# TTFT.net
KiCad netlist of a schematic drawn in Altium Designer
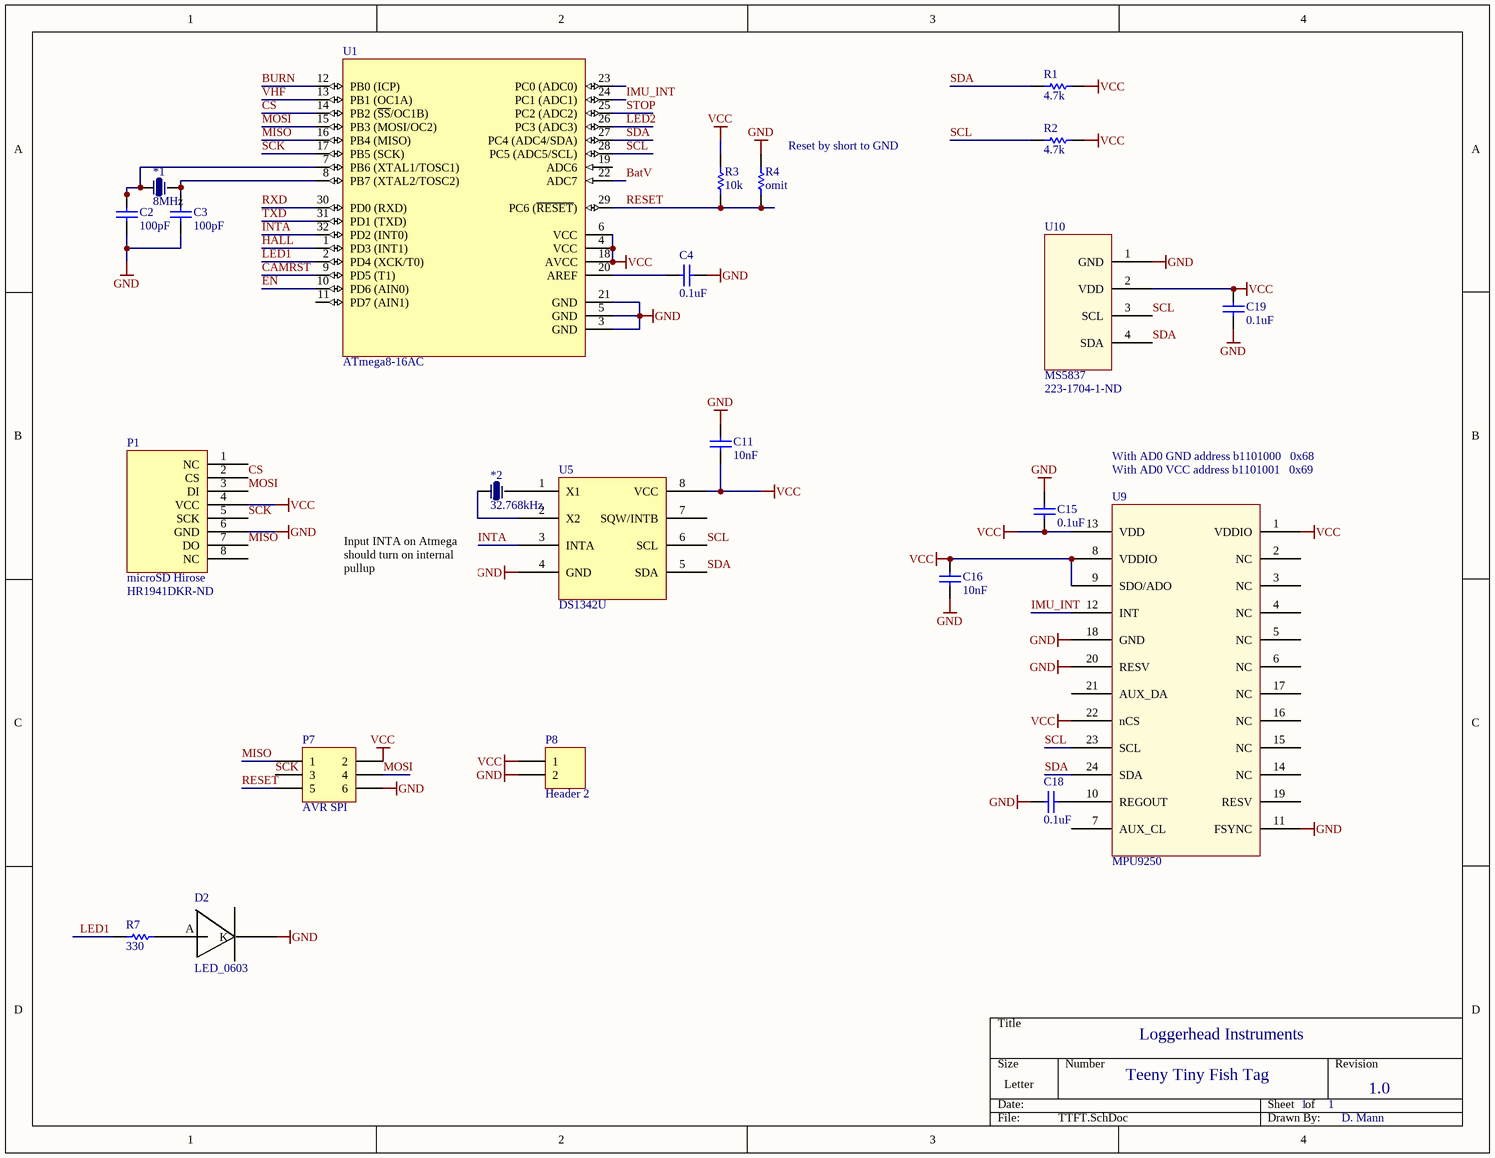
[diagram p0: TTFT.SchDoc]

(export (version "E")
  (design (tool "Eeschema 10.0.6"))
  (components
    (comp (ref "*1") (value "8MHz") (footprint "XTAL-ABM3") (libsource (lib "Loggerhead") (part "XTAL-ABM3")))
    (comp (ref "*2")
      (value "32.768kHz")
      (footprint "XTAL-ABS06")
      (libsource (lib "Loggerhead") (part "XTAL_ABS06"))
    )
    (comp (ref "C2")
      (value "100pF")
      (footprint "0402")
      (description "Ceramic Chip Capacitor - Standard")
      (fields (field (name "PUBLISHER") "Altium Limited"))
      (libsource (lib "KEMET Chip Capacitor") (part "C0402"))
    )
    (comp (ref "C3")
      (value "100pF")
      (footprint "0402")
      (description "Ceramic Chip Capacitor - Standard")
      (fields (field (name "PUBLISHER") "Altium Limited"))
      (libsource (lib "KEMET Chip Capacitor") (part "C0402"))
    )
    (comp (ref "C4")
      (value "0.1uF")
      (footprint "0402")
      (description "Ceramic Chip Capacitor - Standard")
      (fields (field (name "PUBLISHER") "Altium Limited"))
      (libsource (lib "KEMET Chip Capacitor") (part "C0402"))
    )
    (comp (ref "C11")
      (value "10nF")
      (footprint "0402")
      (description "Ceramic Chip Capacitor - Standard")
      (fields (field (name "PUBLISHER") "Altium Limited"))
      (libsource (lib "KEMET Chip Capacitor") (part "C0402"))
    )
    (comp (ref "C15")
      (value "0.1uF")
      (footprint "0402")
      (description "Ceramic Chip Capacitor - Standard")
      (fields (field (name "PUBLISHER") "Altium Limited"))
      (libsource (lib "KEMET Chip Capacitor") (part "C0402"))
    )
    (comp (ref "C16")
      (value "10nF")
      (footprint "0402")
      (description "Ceramic Chip Capacitor - Standard")
      (fields (field (name "PUBLISHER") "Altium Limited"))
      (libsource (lib "KEMET Chip Capacitor") (part "C0402"))
    )
    (comp (ref "C18")
      (value "0.1uF")
      (footprint "0402")
      (description "Ceramic Chip Capacitor - Standard")
      (fields (field (name "PUBLISHER") "Altium Limited"))
      (libsource (lib "KEMET Chip Capacitor") (part "C0402"))
    )
    (comp (ref "C19")
      (value "0.1uF")
      (footprint "0402")
      (description "Ceramic Chip Capacitor - Standard")
      (fields (field (name "PUBLISHER") "Altium Limited"))
      (libsource (lib "KEMET Chip Capacitor") (part "C0402"))
    )
    (comp (ref "D2")
      (value "LED_0603")
      (footprint "Diode0603")
      (libsource (lib "Loggerhead") (part "LED_0603"))
    )
    (comp (ref "P1")
      (value "microSD Hirose")
      (footprint "DM3D microSD")
      (fields (field (name "SUPPLIER PART NUMBER 1") "HR1941DKR-ND"))
      (libsource (lib "Loggerhead") (part "microSD Hirose"))
    )
    (comp (ref "P7")
      (value "AVR SPI")
      (footprint "HDR2X3")
      (description "Header, 3-Pin, Dual row")
      (fields (field (name "PUBLISHER") "Altium Limited"))
      (libsource (lib "Miscellaneous Connectors") (part "Header 3X2"))
    )
    (comp (ref "P8")
      (value "Header 2")
      (footprint "HDR1X2")
      (description "Header, 2-Pin")
      (fields (field (name "PUBLISHER") "Altium Limited"))
      (libsource (lib "Miscellaneous Connectors") (part "Header 2"))
    )
    (comp (ref "R1")
      (value "4.7k")
      (footprint "3-0603")
      (fields (field (name "PUBLISHER") "Altium Limited"))
      (libsource (lib "Panasonic Resistor") (part "ERJ3RK"))
    )
    (comp (ref "R2")
      (value "4.7k")
      (footprint "3-0603")
      (fields (field (name "PUBLISHER") "Altium Limited"))
      (libsource (lib "Panasonic Resistor") (part "ERJ3RK"))
    )
    (comp (ref "R3")
      (value "10k")
      (footprint "3-0603")
      (fields (field (name "PUBLISHER") "Altium Limited"))
      (libsource (lib "Panasonic Resistor") (part "ERJ3RK"))
    )
    (comp (ref "R4")
      (value "omit")
      (footprint "3-0603")
      (fields (field (name "PUBLISHER") "Altium Limited"))
      (libsource (lib "Panasonic Resistor") (part "ERJ3RK"))
    )
    (comp (ref "R7")
      (value "330")
      (footprint "3-0603")
      (fields (field (name "PUBLISHER") "Altium Limited"))
      (libsource (lib "Panasonic Resistor") (part "ERJ3RK"))
    )
    (comp (ref "U1")
      (value "ATmega8-16AC")
      (footprint "32M1-A_M")
      (description "8-Bit AVR Microcontroller with 8K Bytes of In-System Programmable Flash Memory")
      (fields (field (name "PUBLISHER") "Altium Limited"))
      (libsource (lib "Atmel Microcontroller 8-Bit AVR") (part "ATmega8-16AC"))
    )
    (comp (ref "U5") (value "DS1342U") (footprint "uSOP8") (libsource (lib "Loggerhead") (part "DS1337")))
    (comp (ref "U9")
      (value "MPU9250")
      (footprint "MPU6500")
      (description "Invensense")
      (libsource (lib "Loggerhead") (part "MPU-9250"))
    )
    (comp (ref "U10")
      (value "MS5837")
      (footprint "MS5837")
      (description "Pressure/Temp")
      (fields (field (name "SUPPLIER PART NUMBER 1") "223-1704-1-ND"))
      (libsource (lib "Loggerhead") (part "MS5837"))
    )
  )
  (nets
    (net (code "1") (name "/BURN") (class "Default")
      (node (ref "U1") (pin "12") (pinfunction "PB0_(ICP)_12") (pintype "bidirectional"))
    )
    (net (code "2") (name "/BatV") (class "Default")
      (node (ref "U1") (pin "22") (pinfunction "ADC7_22") (pintype "input"))
    )
    (net (code "3") (name "/CAMRST") (class "Default")
      (node (ref "U1") (pin "9") (pinfunction "PD5_(T1)_9") (pintype "bidirectional"))
    )
    (net (code "4") (name "/CS") (class "Default")
      (node (ref "P1") (pin "2") (pinfunction "CS_2") (pintype "passive"))
      (node (ref "U1") (pin "14") (pinfunction "PB2_(~{SS}/OC1B)_14") (pintype "bidirectional"))
    )
    (net (code "5") (name "/EN") (class "Default")
      (node (ref "U1") (pin "10") (pinfunction "PD6_(AIN0)_10") (pintype "bidirectional"))
    )
    (net (code "6") (name "/HALL") (class "Default")
      (node (ref "U1") (pin "1") (pinfunction "PD3_(INT1)_1") (pintype "bidirectional"))
    )
    (net (code "7") (name "/IMU_INT") (class "Default")
      (node (ref "U1") (pin "24") (pinfunction "PC1_(ADC1)_24") (pintype "bidirectional"))
      (node (ref "U9") (pin "12") (pinfunction "INT_12") (pintype "passive"))
    )
    (net (code "8") (name "/INTA") (class "Default")
      (node (ref "U1") (pin "32") (pinfunction "PD2_(INT0)_32") (pintype "bidirectional"))
      (node (ref "U5") (pin "3") (pinfunction "INTA_3") (pintype "passive"))
    )
    (net (code "9") (name "/LED1") (class "Default")
      (node (ref "R7") (pin "1") (pinfunction "1_1") (pintype "passive"))
      (node (ref "U1") (pin "2") (pinfunction "PD4_(XCK/T0)_2") (pintype "bidirectional"))
    )
    (net (code "10") (name "/LED2") (class "Default")
      (node (ref "U1") (pin "26") (pinfunction "PC3_(ADC3)_26") (pintype "bidirectional"))
    )
    (net (code "11") (name "/MISO") (class "Default")
      (node (ref "P1") (pin "7") (pinfunction "DO_7") (pintype "passive"))
      (node (ref "P7") (pin "1") (pinfunction "1_1") (pintype "passive"))
      (node (ref "U1") (pin "16") (pinfunction "PB4_(MISO)_16") (pintype "bidirectional"))
    )
    (net (code "12") (name "/MOSI") (class "Default")
      (node (ref "P1") (pin "3") (pinfunction "DI_3") (pintype "passive"))
      (node (ref "P7") (pin "4") (pinfunction "4_4") (pintype "passive"))
      (node (ref "U1") (pin "15") (pinfunction "PB3_(MOSI/OC2)_15") (pintype "bidirectional"))
    )
    (net (code "13") (name "/RESET") (class "Default")
      (node (ref "P7") (pin "5") (pinfunction "5_5") (pintype "passive"))
      (node (ref "R3") (pin "1") (pinfunction "1_1") (pintype "passive"))
      (node (ref "R4") (pin "1") (pinfunction "1_1") (pintype "passive"))
      (node (ref "U1") (pin "29") (pinfunction "PC6_(~{RESET})_29") (pintype "bidirectional"))
    )
    (net (code "14") (name "/RXD") (class "Default")
      (node (ref "U1") (pin "30") (pinfunction "PD0_(RXD)_30") (pintype "bidirectional"))
    )
    (net (code "15") (name "/SCK") (class "Default")
      (node (ref "P1") (pin "5") (pinfunction "SCK_5") (pintype "passive"))
      (node (ref "P7") (pin "3") (pinfunction "3_3") (pintype "passive"))
      (node (ref "U1") (pin "17") (pinfunction "PB5_(SCK)_17") (pintype "bidirectional"))
    )
    (net (code "16") (name "/SCL") (class "Default")
      (node (ref "R2") (pin "1") (pinfunction "1_1") (pintype "passive"))
      (node (ref "U1") (pin "28") (pinfunction "PC5_(ADC5/SCL)_28") (pintype "bidirectional"))
      (node (ref "U10") (pin "3") (pinfunction "SCL_3") (pintype "passive"))
      (node (ref "U5") (pin "6") (pinfunction "SCL_6") (pintype "passive"))
      (node (ref "U9") (pin "23") (pinfunction "SCL_23") (pintype "passive"))
    )
    (net (code "17") (name "/SDA") (class "Default")
      (node (ref "R1") (pin "1") (pinfunction "1_1") (pintype "passive"))
      (node (ref "U1") (pin "27") (pinfunction "PC4_(ADC4/SDA)_27") (pintype "bidirectional"))
      (node (ref "U10") (pin "4") (pinfunction "SDA_4") (pintype "passive"))
      (node (ref "U5") (pin "5") (pinfunction "SDA_5") (pintype "passive"))
      (node (ref "U9") (pin "24") (pinfunction "SDA_24") (pintype "passive"))
    )
    (net (code "18") (name "/STOP") (class "Default")
      (node (ref "U1") (pin "25") (pinfunction "PC2_(ADC2)_25") (pintype "bidirectional"))
    )
    (net (code "19") (name "/TXD") (class "Default")
      (node (ref "U1") (pin "31") (pinfunction "PD1_(TXD)_31") (pintype "bidirectional"))
    )
    (net (code "20") (name "/VHF") (class "Default")
      (node (ref "U1") (pin "13") (pinfunction "PB1_(OC1A)_13") (pintype "bidirectional"))
    )
    (net (code "21") (name "GND") (class "Default")
      (node (ref "C11") (pin "1") (pinfunction "1_1") (pintype "passive"))
      (node (ref "C15") (pin "2") (pinfunction "2_2") (pintype "passive"))
      (node (ref "C16") (pin "2") (pinfunction "2_2") (pintype "passive"))
      (node (ref "C18") (pin "1") (pinfunction "1_1") (pintype "passive"))
      (node (ref "C19") (pin "1") (pinfunction "1_1") (pintype "passive"))
      (node (ref "C2") (pin "1") (pinfunction "1_1") (pintype "passive"))
      (node (ref "C3") (pin "1") (pinfunction "1_1") (pintype "passive"))
      (node (ref "C4") (pin "2") (pinfunction "2_2") (pintype "passive"))
      (node (ref "D2") (pin "K") (pinfunction "K_K") (pintype "passive"))
      (node (ref "P1") (pin "6") (pinfunction "GND_6") (pintype "passive"))
      (node (ref "P7") (pin "6") (pinfunction "6_6") (pintype "passive"))
      (node (ref "P8") (pin "2") (pinfunction "2_2") (pintype "passive"))
      (node (ref "R4") (pin "2") (pinfunction "2_2") (pintype "passive"))
      (node (ref "U1") (pin "21") (pinfunction "GND_21") (pintype "power_in"))
      (node (ref "U1") (pin "3") (pinfunction "GND_3") (pintype "power_in"))
      (node (ref "U1") (pin "5") (pinfunction "GND_5") (pintype "power_in"))
      (node (ref "U10") (pin "1") (pinfunction "GND_1") (pintype "passive"))
      (node (ref "U5") (pin "4") (pinfunction "GND_4") (pintype "passive"))
      (node (ref "U9") (pin "11") (pinfunction "FSYNC_11") (pintype "passive"))
      (node (ref "U9") (pin "18") (pinfunction "GND_18") (pintype "passive"))
      (node (ref "U9") (pin "20") (pinfunction "RESV_20") (pintype "passive"))
    )
    (net (code "22") (name "Net-(D2-PadA)") (class "Default")
      (node (ref "D2") (pin "A") (pinfunction "A_A") (pintype "passive"))
      (node (ref "R7") (pin "2") (pinfunction "2_2") (pintype "passive"))
    )
    (net (code "23") (name "Net-(U1-AREF)") (class "Default")
      (node (ref "C4") (pin "1") (pinfunction "1_1") (pintype "passive"))
      (node (ref "U1") (pin "20") (pinfunction "AREF_20") (pintype "passive"))
    )
    (net (code "24") (name "Net-(U1-PB6_(XTAL1{slash}TOSC1))") (class "Default")
      (node (ref "*1") (pin "1") (pinfunction "1_1") (pintype "passive"))
      (node (ref "C2") (pin "2") (pinfunction "2_2") (pintype "passive"))
      (node (ref "U1") (pin "7") (pinfunction "PB6_(XTAL1/TOSC1)_7") (pintype "bidirectional"))
    )
    (net (code "25") (name "Net-(U1-PB7_(XTAL2{slash}TOSC2))") (class "Default")
      (node (ref "*1") (pin "2") (pinfunction "2_2") (pintype "passive"))
      (node (ref "C3") (pin "2") (pinfunction "2_2") (pintype "passive"))
      (node (ref "U1") (pin "8") (pinfunction "PB7_(XTAL2/TOSC2)_8") (pintype "bidirectional"))
    )
    (net (code "26") (name "Net-(U5-X1)") (class "Default")
      (node (ref "*2") (pin "2") (pinfunction "2_2") (pintype "passive"))
      (node (ref "U5") (pin "1") (pinfunction "X1_1") (pintype "passive"))
    )
    (net (code "27") (name "Net-(U5-X2)") (class "Default")
      (node (ref "*2") (pin "1") (pinfunction "1_1") (pintype "passive"))
      (node (ref "U5") (pin "2") (pinfunction "X2_2") (pintype "passive"))
    )
    (net (code "28") (name "Net-(U9-REGOUT)") (class "Default")
      (node (ref "C18") (pin "2") (pinfunction "2_2") (pintype "passive"))
      (node (ref "U9") (pin "10") (pinfunction "REGOUT_10") (pintype "passive"))
    )
    (net (code "29") (name "VCC") (class "Default")
      (node (ref "C11") (pin "2") (pinfunction "2_2") (pintype "passive"))
      (node (ref "C15") (pin "1") (pinfunction "1_1") (pintype "passive"))
      (node (ref "C16") (pin "1") (pinfunction "1_1") (pintype "passive"))
      (node (ref "C19") (pin "2") (pinfunction "2_2") (pintype "passive"))
      (node (ref "P1") (pin "4") (pinfunction "VCC_4") (pintype "passive"))
      (node (ref "P7") (pin "2") (pinfunction "2_2") (pintype "passive"))
      (node (ref "P8") (pin "1") (pinfunction "1_1") (pintype "passive"))
      (node (ref "R1") (pin "2") (pinfunction "2_2") (pintype "passive"))
      (node (ref "R2") (pin "2") (pinfunction "2_2") (pintype "passive"))
      (node (ref "R3") (pin "2") (pinfunction "2_2") (pintype "passive"))
      (node (ref "U1") (pin "18") (pinfunction "AVCC_18") (pintype "power_in"))
      (node (ref "U1") (pin "4") (pinfunction "VCC_4") (pintype "power_in"))
      (node (ref "U1") (pin "6") (pinfunction "VCC_6") (pintype "power_in"))
      (node (ref "U10") (pin "2") (pinfunction "VDD_2") (pintype "passive"))
      (node (ref "U5") (pin "8") (pinfunction "VCC_8") (pintype "power_in"))
      (node (ref "U9") (pin "1") (pinfunction "VDDIO_1") (pintype "passive"))
      (node (ref "U9") (pin "13") (pinfunction "VDD_13") (pintype "passive"))
      (node (ref "U9") (pin "22") (pinfunction "nCS_22") (pintype "passive"))
      (node (ref "U9") (pin "8") (pinfunction "VDDIO_8") (pintype "passive"))
      (node (ref "U9") (pin "9") (pinfunction "SDO/ADO_9") (pintype "passive"))
    )
    (net (code "30") (name "unconnected-(P1-NC-Pad1)") (class "Default")
      (node (ref "P1") (pin "1") (pinfunction "NC_1") (pintype "passive"))
    )
    (net (code "31") (name "unconnected-(P1-NC-Pad8)") (class "Default")
      (node (ref "P1") (pin "8") (pinfunction "NC_8") (pintype "passive"))
    )
    (net (code "32") (name "unconnected-(U1-ADC6-Pad19)") (class "Default")
      (node (ref "U1") (pin "19") (pinfunction "ADC6_19") (pintype "input"))
    )
    (net (code "33") (name "unconnected-(U1-PC0_(ADC0)-Pad23)") (class "Default")
      (node (ref "U1") (pin "23") (pinfunction "PC0_(ADC0)_23") (pintype "bidirectional"))
    )
    (net (code "34") (name "unconnected-(U1-PD7_(AIN1)-Pad11)") (class "Default")
      (node (ref "U1") (pin "11") (pinfunction "PD7_(AIN1)_11") (pintype "bidirectional"))
    )
    (net (code "35") (name "unconnected-(U5-SQW{slash}INTB-Pad7)") (class "Default")
      (node (ref "U5") (pin "7") (pinfunction "SQW/INTB_7") (pintype "passive"))
    )
    (net (code "36") (name "unconnected-(U9-AUX_CL-Pad7)") (class "Default")
      (node (ref "U9") (pin "7") (pinfunction "AUX_CL_7") (pintype "passive"))
    )
    (net (code "37") (name "unconnected-(U9-AUX_DA-Pad21)") (class "Default")
      (node (ref "U9") (pin "21") (pinfunction "AUX_DA_21") (pintype "passive"))
    )
    (net (code "38") (name "unconnected-(U9-NC-Pad2)") (class "Default")
      (node (ref "U9") (pin "2") (pinfunction "NC_2") (pintype "passive"))
    )
    (net (code "39") (name "unconnected-(U9-NC-Pad3)") (class "Default")
      (node (ref "U9") (pin "3") (pinfunction "NC_3") (pintype "passive"))
    )
    (net (code "40") (name "unconnected-(U9-NC-Pad4)") (class "Default")
      (node (ref "U9") (pin "4") (pinfunction "NC_4") (pintype "passive"))
    )
    (net (code "41") (name "unconnected-(U9-NC-Pad5)") (class "Default")
      (node (ref "U9") (pin "5") (pinfunction "NC_5") (pintype "passive"))
    )
    (net (code "42") (name "unconnected-(U9-NC-Pad6)") (class "Default")
      (node (ref "U9") (pin "6") (pinfunction "NC_6") (pintype "passive"))
    )
    (net (code "43") (name "unconnected-(U9-NC-Pad14)") (class "Default")
      (node (ref "U9") (pin "14") (pinfunction "NC_14") (pintype "passive"))
    )
    (net (code "44") (name "unconnected-(U9-NC-Pad15)") (class "Default")
      (node (ref "U9") (pin "15") (pinfunction "NC_15") (pintype "passive"))
    )
    (net (code "45") (name "unconnected-(U9-NC-Pad16)") (class "Default")
      (node (ref "U9") (pin "16") (pinfunction "NC_16") (pintype "passive"))
    )
    (net (code "46") (name "unconnected-(U9-NC-Pad17)") (class "Default")
      (node (ref "U9") (pin "17") (pinfunction "NC_17") (pintype "passive"))
    )
    (net (code "47") (name "unconnected-(U9-RESV-Pad19)") (class "Default")
      (node (ref "U9") (pin "19") (pinfunction "RESV_19") (pintype "passive"))
    )
  )
)
